# 02_sensor.net
KiCad netlist of a schematic drawn in Altium Designer
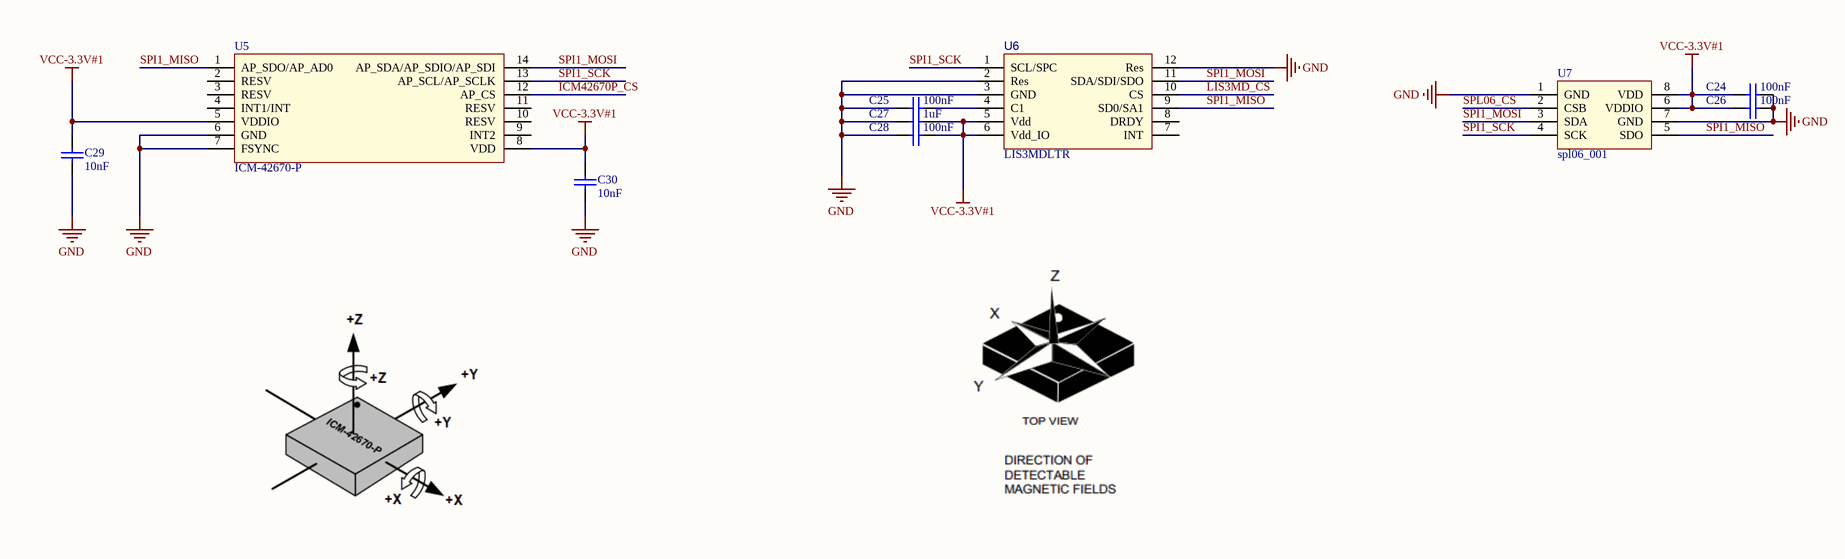
[diagram p0: 02_sensor.SchDoc]

(export (version "E")
  (design (tool "Eeschema 10.0.6"))
  (components
    (comp (ref "C24")
      (value "100nF")
      (footprint "0603-C")
      (description "贴片电容")
      (libsource (lib "封装库") (part "C"))
    )
    (comp (ref "C25")
      (value "100nF")
      (footprint "0603-C")
      (description "贴片电容")
      (libsource (lib "封装库") (part "C"))
    )
    (comp (ref "C26")
      (value "100nF")
      (footprint "0603-C")
      (description "贴片电容")
      (libsource (lib "封装库") (part "C"))
    )
    (comp (ref "C27")
      (value "1uF")
      (footprint "0603-C")
      (description "贴片电容")
      (libsource (lib "封装库") (part "C"))
    )
    (comp (ref "C28")
      (value "100nF")
      (footprint "0603-C")
      (description "贴片电容")
      (libsource (lib "封装库") (part "C"))
    )
    (comp (ref "C29")
      (value "10nF")
      (footprint "0603-C")
      (description "贴片电容")
      (libsource (lib "封装库") (part "C"))
    )
    (comp (ref "C30")
      (value "10nF")
      (footprint "0603-C")
      (description "贴片电容")
      (libsource (lib "封装库") (part "C"))
    )
    (comp (ref "U5")
      (value "ICM-42670-P")
      (footprint "ICM42670P")
      (fields (field (name "MANUFACTURER") "TDK InvenSense(应美盛)"))
      (libsource (lib "封装库") (part "ICM-42670-P"))
    )
    (comp (ref "U6")
      (value "LIS3MDLTR")
      (footprint "LIS3MDLTR")
      (fields (field (name "MANUFACTURER") "ST(意法半导体)"))
      (libsource (lib "封装库") (part "LIS3MDLTR"))
    )
    (comp (ref "U7")
      (value "spl06_001")
      (footprint "SPL06")
      (description "气压计")
      (libsource (lib "封装库") (part "SPL06_001"))
    )
  )
  (nets
    (net (code "1") (name "/ICM42670P_CS") (class "Default")
      (node (ref "U5") (pin "12") (pinfunction "AP_CS_12") (pintype "passive"))
    )
    (net (code "2") (name "/LIS3MD_CS") (class "Default")
      (node (ref "U6") (pin "10") (pinfunction "CS_10") (pintype "passive"))
    )
    (net (code "3") (name "/SPI1_MISO") (class "Default")
      (node (ref "U5") (pin "1") (pinfunction "AP_SDO/AP_AD0_1") (pintype "passive"))
      (node (ref "U6") (pin "9") (pinfunction "SD0/SA1_9") (pintype "passive"))
      (node (ref "U7") (pin "5") (pinfunction "SDO_5") (pintype "passive"))
    )
    (net (code "4") (name "/SPI1_MOSI") (class "Default")
      (node (ref "U5") (pin "14") (pinfunction "AP_SDA/AP_SDIO/AP_SDI_14") (pintype "passive"))
      (node (ref "U6") (pin "11") (pinfunction "SDA/SDI/SDO_11") (pintype "passive"))
      (node (ref "U7") (pin "3") (pinfunction "SDA_3") (pintype "passive"))
    )
    (net (code "5") (name "/SPI1_SCK") (class "Default")
      (node (ref "U5") (pin "13") (pinfunction "AP_SCL/AP_SCLK_13") (pintype "passive"))
      (node (ref "U6") (pin "1") (pinfunction "SCL/SPC_1") (pintype "passive"))
      (node (ref "U7") (pin "4") (pinfunction "SCK_4") (pintype "passive"))
    )
    (net (code "6") (name "/SPL06_CS") (class "Default")
      (node (ref "U7") (pin "2") (pinfunction "CSB_2") (pintype "passive"))
    )
    (net (code "7") (name "GND") (class "Default")
      (node (ref "C24") (pin "2") (pinfunction "2_2") (pintype "passive"))
      (node (ref "C25") (pin "1") (pinfunction "1_1") (pintype "passive"))
      (node (ref "C26") (pin "2") (pinfunction "2_2") (pintype "passive"))
      (node (ref "C27") (pin "1") (pinfunction "1_1") (pintype "passive"))
      (node (ref "C28") (pin "1") (pinfunction "1_1") (pintype "passive"))
      (node (ref "C29") (pin "1") (pinfunction "1_1") (pintype "passive"))
      (node (ref "C30") (pin "1") (pinfunction "1_1") (pintype "passive"))
      (node (ref "U5") (pin "6") (pinfunction "GND_6") (pintype "passive"))
      (node (ref "U5") (pin "7") (pinfunction "FSYNC_7") (pintype "passive"))
      (node (ref "U6") (pin "12") (pinfunction "Res_12") (pintype "passive"))
      (node (ref "U6") (pin "2") (pinfunction "Res_2") (pintype "passive"))
      (node (ref "U6") (pin "3") (pinfunction "GND_3") (pintype "passive"))
      (node (ref "U7") (pin "1") (pinfunction "GND_1") (pintype "passive"))
      (node (ref "U7") (pin "7") (pinfunction "GND_7") (pintype "passive"))
    )
    (net (code "8") (name "Net-(U6-C1)") (class "Default")
      (node (ref "C25") (pin "2") (pinfunction "2_2") (pintype "passive"))
      (node (ref "U6") (pin "4") (pinfunction "C1_4") (pintype "passive"))
    )
    (net (code "9") (name "VCC-3.3V#1") (class "Default")
      (node (ref "C24") (pin "1") (pinfunction "1_1") (pintype "passive"))
      (node (ref "C26") (pin "1") (pinfunction "1_1") (pintype "passive"))
      (node (ref "C27") (pin "2") (pinfunction "2_2") (pintype "passive"))
      (node (ref "C28") (pin "2") (pinfunction "2_2") (pintype "passive"))
      (node (ref "C29") (pin "2") (pinfunction "2_2") (pintype "passive"))
      (node (ref "C30") (pin "2") (pinfunction "2_2") (pintype "passive"))
      (node (ref "U5") (pin "5") (pinfunction "VDDIO_5") (pintype "passive"))
      (node (ref "U5") (pin "8") (pinfunction "VDD_8") (pintype "passive"))
      (node (ref "U6") (pin "5") (pinfunction "Vdd_5") (pintype "passive"))
      (node (ref "U6") (pin "6") (pinfunction "Vdd_IO_6") (pintype "passive"))
      (node (ref "U7") (pin "6") (pinfunction "VDDIO_6") (pintype "passive"))
      (node (ref "U7") (pin "8") (pinfunction "VDD_8") (pintype "passive"))
    )
    (net (code "10") (name "unconnected-(U5-INT1{slash}INT-Pad4)") (class "Default")
      (node (ref "U5") (pin "4") (pinfunction "INT1/INT_4") (pintype "passive"))
    )
    (net (code "11") (name "unconnected-(U5-INT2-Pad9)") (class "Default")
      (node (ref "U5") (pin "9") (pinfunction "INT2_9") (pintype "passive"))
    )
    (net (code "12") (name "unconnected-(U5-RESV-Pad2)") (class "Default")
      (node (ref "U5") (pin "2") (pinfunction "RESV_2") (pintype "passive"))
    )
    (net (code "13") (name "unconnected-(U5-RESV-Pad3)") (class "Default")
      (node (ref "U5") (pin "3") (pinfunction "RESV_3") (pintype "passive"))
    )
    (net (code "14") (name "unconnected-(U5-RESV-Pad10)") (class "Default")
      (node (ref "U5") (pin "10") (pinfunction "RESV_10") (pintype "passive"))
    )
    (net (code "15") (name "unconnected-(U5-RESV-Pad11)") (class "Default")
      (node (ref "U5") (pin "11") (pinfunction "RESV_11") (pintype "passive"))
    )
    (net (code "16") (name "unconnected-(U6-DRDY-Pad8)") (class "Default")
      (node (ref "U6") (pin "8") (pinfunction "DRDY_8") (pintype "passive"))
    )
    (net (code "17") (name "unconnected-(U6-INT-Pad7)") (class "Default")
      (node (ref "U6") (pin "7") (pinfunction "INT_7") (pintype "passive"))
    )
  )
)
